# Wiegand.net
KiCad netlist of a schematic drawn in EAGLE
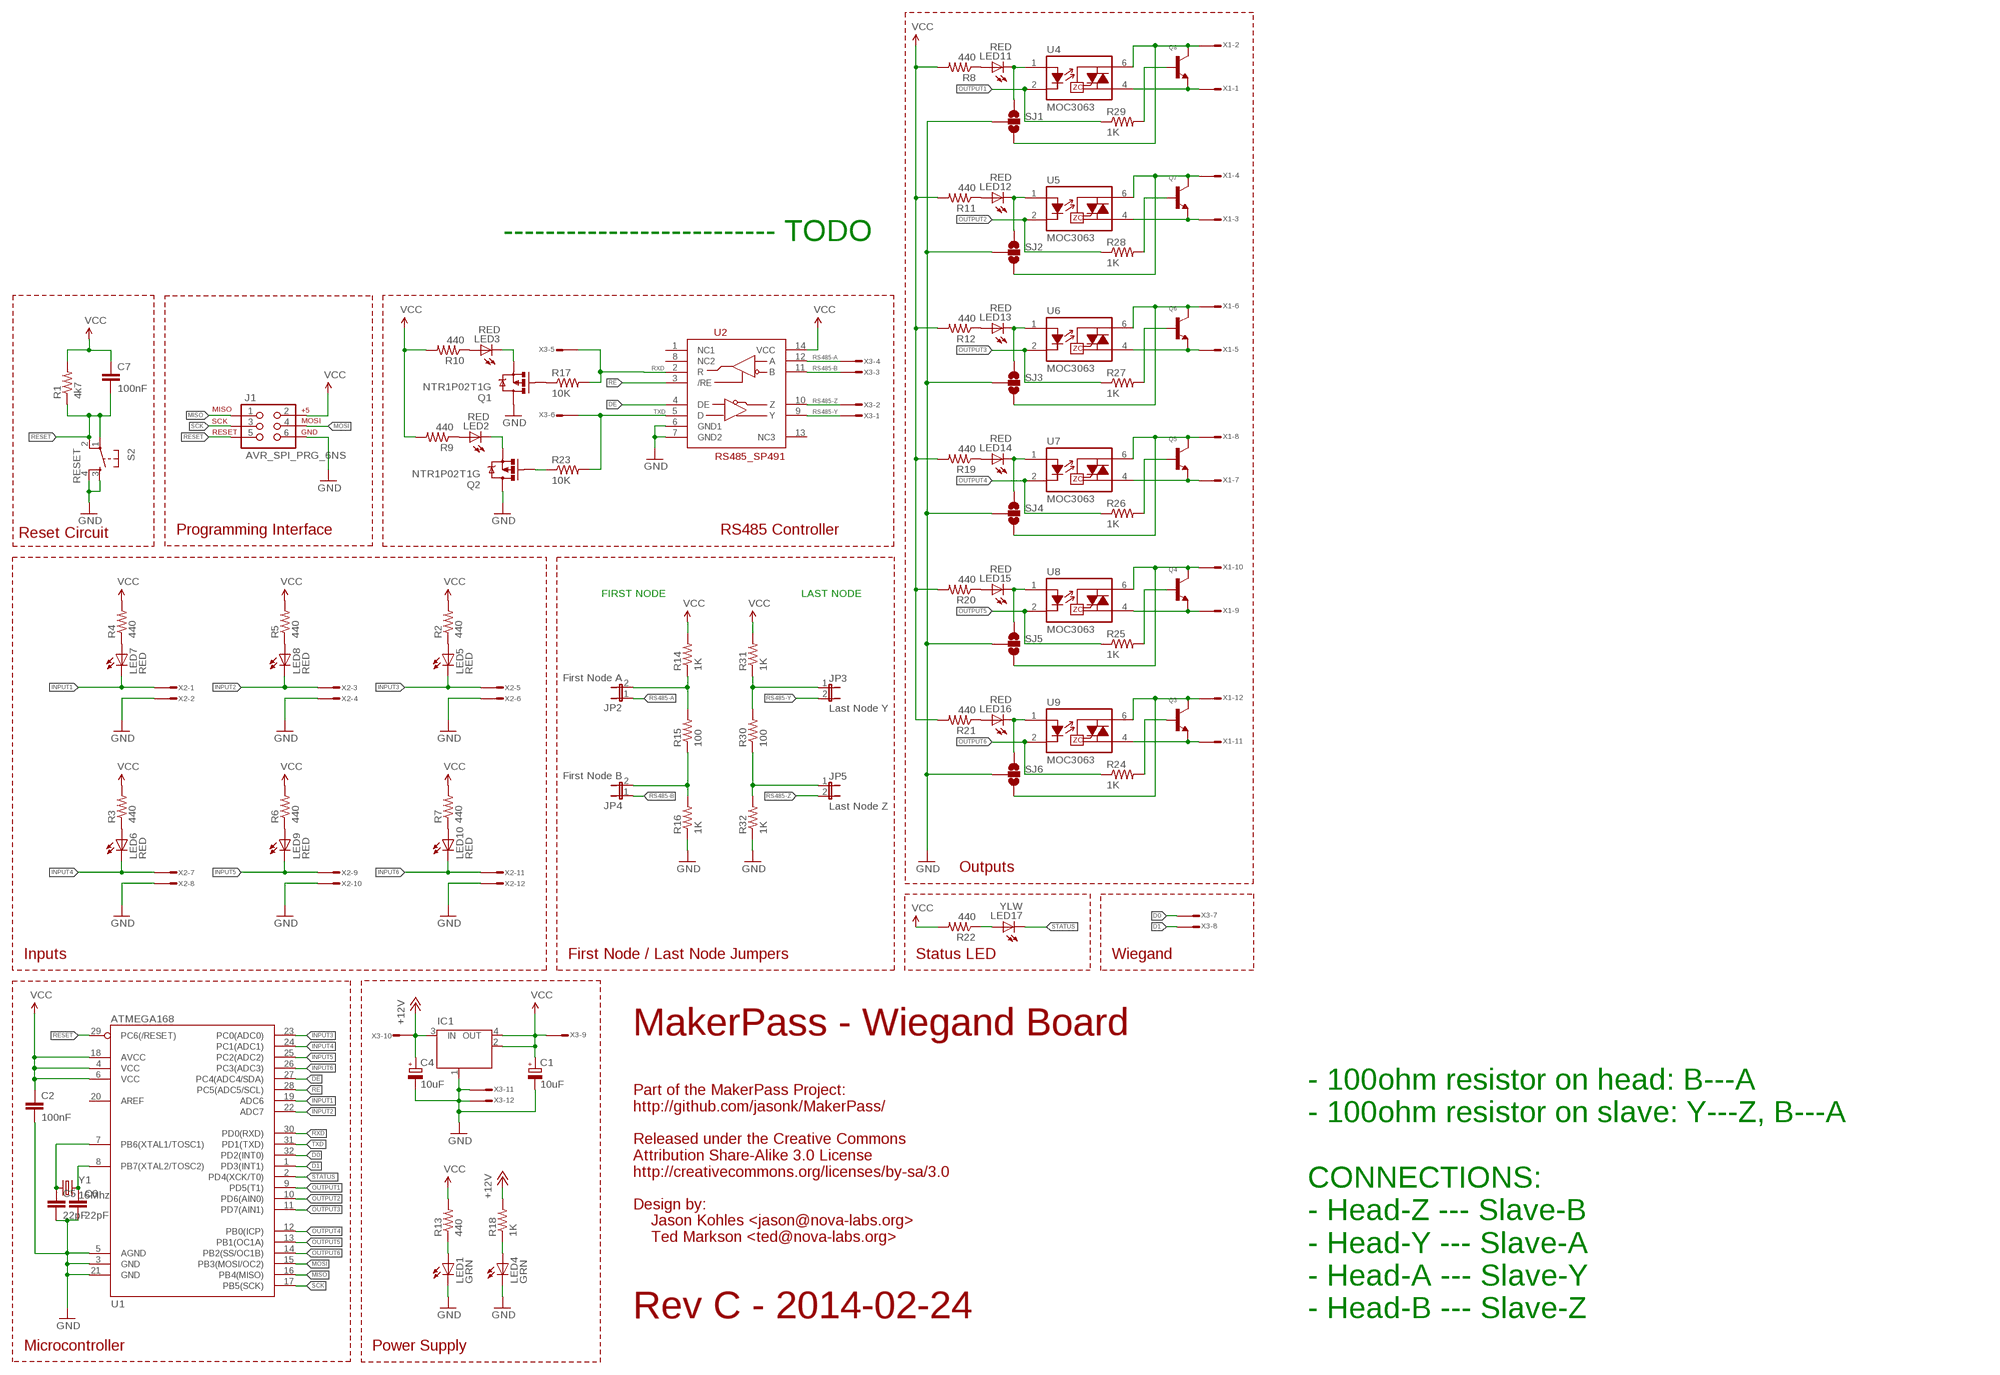
[diagram p0: schematic, sheet 1]

(export (version "E")
  (design (tool "Eeschema 10.0.6"))
  (components
    (comp (ref "C1")
      (value "10uF")
      (footprint "eagle-import:PANASONIC_D")
      (libsource (lib "eagle-import") (part "CPOL-EUD"))
    )
    (comp (ref "C2")
      (value "100nF")
      (footprint "eagle-import:0603-CAP")
      (libsource (lib "eagle-import") (part "CAP0603-CAP"))
    )
    (comp (ref "C4")
      (value "10uF")
      (footprint "eagle-import:PANASONIC_D")
      (libsource (lib "eagle-import") (part "CPOL-EUD"))
    )
    (comp (ref "C5")
      (value "22pF")
      (footprint "eagle-import:0603-CAP")
      (libsource (lib "eagle-import") (part "CAP0603-CAP"))
    )
    (comp (ref "C6")
      (value "22pF")
      (footprint "eagle-import:0603-CAP")
      (libsource (lib "eagle-import") (part "CAP0603-CAP"))
    )
    (comp (ref "C7")
      (value "100nF")
      (footprint "eagle-import:0603-CAP")
      (libsource (lib "eagle-import") (part "CAP0603-CAP"))
    )
    (comp (ref "IC1")
      (value "MC33269ST-3.3T3")
      (footprint "eagle-import:SOT223")
      (libsource (lib "eagle-import") (part "MC33269ST-3.3T3"))
    )
    (comp (ref "J1")
      (value "AVR_SPI_PRG_6NS")
      (footprint "eagle-import:2X3-NS")
      (libsource (lib "eagle-import") (part "AVR_SPI_PRG_6NS"))
    )
    (comp (ref "JP2")
      (value "First Node A")
      (footprint "eagle-import:1X02")
      (libsource (lib "eagle-import") (part "JUMPER-2PTH"))
    )
    (comp (ref "JP3")
      (value "Last Node Y")
      (footprint "eagle-import:1X02")
      (libsource (lib "eagle-import") (part "JUMPER-2PTH"))
    )
    (comp (ref "JP4")
      (value "First Node B")
      (footprint "eagle-import:1X02")
      (libsource (lib "eagle-import") (part "JUMPER-2PTH"))
    )
    (comp (ref "JP5")
      (value "Last Node Z")
      (footprint "eagle-import:1X02")
      (libsource (lib "eagle-import") (part "JUMPER-2PTH"))
    )
    (comp (ref "LED1")
      (value "GRN")
      (footprint "eagle-import:LED-805")
      (libsource (lib "eagle-import") (part "LED-0805"))
    )
    (comp (ref "LED2")
      (value "RED")
      (footprint "eagle-import:LED-805")
      (libsource (lib "eagle-import") (part "LED-0805"))
    )
    (comp (ref "LED3")
      (value "RED")
      (footprint "eagle-import:LED-805")
      (libsource (lib "eagle-import") (part "LED-0805"))
    )
    (comp (ref "LED4")
      (value "GRN")
      (footprint "eagle-import:LED-805")
      (libsource (lib "eagle-import") (part "LED-0805"))
    )
    (comp (ref "LED5")
      (value "RED")
      (footprint "eagle-import:LED-805")
      (libsource (lib "eagle-import") (part "LED-0805"))
    )
    (comp (ref "LED6")
      (value "RED")
      (footprint "eagle-import:LED-805")
      (libsource (lib "eagle-import") (part "LED-0805"))
    )
    (comp (ref "LED7")
      (value "RED")
      (footprint "eagle-import:LED-805")
      (libsource (lib "eagle-import") (part "LED-0805"))
    )
    (comp (ref "LED8")
      (value "RED")
      (footprint "eagle-import:LED-805")
      (libsource (lib "eagle-import") (part "LED-0805"))
    )
    (comp (ref "LED9")
      (value "RED")
      (footprint "eagle-import:LED-805")
      (libsource (lib "eagle-import") (part "LED-0805"))
    )
    (comp (ref "LED10")
      (value "RED")
      (footprint "eagle-import:LED-805")
      (libsource (lib "eagle-import") (part "LED-0805"))
    )
    (comp (ref "LED11")
      (value "RED")
      (footprint "eagle-import:LED-805")
      (libsource (lib "eagle-import") (part "LED-0805"))
    )
    (comp (ref "LED12")
      (value "RED")
      (footprint "eagle-import:LED-805")
      (libsource (lib "eagle-import") (part "LED-0805"))
    )
    (comp (ref "LED13")
      (value "RED")
      (footprint "eagle-import:LED-805")
      (libsource (lib "eagle-import") (part "LED-0805"))
    )
    (comp (ref "LED14")
      (value "RED")
      (footprint "eagle-import:LED-805")
      (libsource (lib "eagle-import") (part "LED-0805"))
    )
    (comp (ref "LED15")
      (value "RED")
      (footprint "eagle-import:LED-805")
      (libsource (lib "eagle-import") (part "LED-0805"))
    )
    (comp (ref "LED16")
      (value "RED")
      (footprint "eagle-import:LED-805")
      (libsource (lib "eagle-import") (part "LED-0805"))
    )
    (comp (ref "LED17")
      (value "YLW")
      (footprint "eagle-import:LED-805")
      (libsource (lib "eagle-import") (part "LED-0805"))
    )
    (comp (ref "Q1")
      (value "NTR1P02T1G")
      (footprint "eagle-import:SOT23-3")
      (libsource (lib "eagle-import") (part "MOSFET-PCHANNELSMD"))
    )
    (comp (ref "Q2")
      (value "NTR1P02T1G")
      (footprint "eagle-import:SOT23-3")
      (libsource (lib "eagle-import") (part "MOSFET-PCHANNELSMD"))
    )
    (comp (ref "Q3")
      (value "NPN-BEC-SOT23-3")
      (footprint "eagle-import:SOT23-3")
      (libsource (lib "eagle-import") (part "NPN-BEC-SOT23-3"))
    )
    (comp (ref "Q4")
      (value "NPN-BEC-SOT23-3")
      (footprint "eagle-import:SOT23-3")
      (libsource (lib "eagle-import") (part "NPN-BEC-SOT23-3"))
    )
    (comp (ref "Q5")
      (value "NPN-BEC-SOT23-3")
      (footprint "eagle-import:SOT23-3")
      (libsource (lib "eagle-import") (part "NPN-BEC-SOT23-3"))
    )
    (comp (ref "Q6")
      (value "NPN-BEC-SOT23-3")
      (footprint "eagle-import:SOT23-3")
      (libsource (lib "eagle-import") (part "NPN-BEC-SOT23-3"))
    )
    (comp (ref "Q7")
      (value "NPN-BEC-SOT23-3")
      (footprint "eagle-import:SOT23-3")
      (libsource (lib "eagle-import") (part "NPN-BEC-SOT23-3"))
    )
    (comp (ref "Q8")
      (value "NPN-BEC-SOT23-3")
      (footprint "eagle-import:SOT23-3")
      (libsource (lib "eagle-import") (part "NPN-BEC-SOT23-3"))
    )
    (comp (ref "R1")
      (value "4k7")
      (footprint "eagle-import:0603-RES")
      (libsource (lib "eagle-import") (part "RESISTOR0603-RES"))
    )
    (comp (ref "R2")
      (value "440")
      (footprint "eagle-import:0603-RES")
      (libsource (lib "eagle-import") (part "RESISTOR0603-RES"))
    )
    (comp (ref "R3")
      (value "440")
      (footprint "eagle-import:0603-RES")
      (libsource (lib "eagle-import") (part "RESISTOR0603-RES"))
    )
    (comp (ref "R4")
      (value "440")
      (footprint "eagle-import:0603-RES")
      (libsource (lib "eagle-import") (part "RESISTOR0603-RES"))
    )
    (comp (ref "R5")
      (value "440")
      (footprint "eagle-import:0603-RES")
      (libsource (lib "eagle-import") (part "RESISTOR0603-RES"))
    )
    (comp (ref "R6")
      (value "440")
      (footprint "eagle-import:0603-RES")
      (libsource (lib "eagle-import") (part "RESISTOR0603-RES"))
    )
    (comp (ref "R7")
      (value "440")
      (footprint "eagle-import:0603-RES")
      (libsource (lib "eagle-import") (part "RESISTOR0603-RES"))
    )
    (comp (ref "R8")
      (value "440")
      (footprint "eagle-import:0603-RES")
      (libsource (lib "eagle-import") (part "RESISTOR0603-RES"))
    )
    (comp (ref "R9")
      (value "440")
      (footprint "eagle-import:0603-RES")
      (libsource (lib "eagle-import") (part "RESISTOR0603-RES"))
    )
    (comp (ref "R10")
      (value "440")
      (footprint "eagle-import:0603-RES")
      (libsource (lib "eagle-import") (part "RESISTOR0603-RES"))
    )
    (comp (ref "R11")
      (value "440")
      (footprint "eagle-import:0603-RES")
      (libsource (lib "eagle-import") (part "RESISTOR0603-RES"))
    )
    (comp (ref "R12")
      (value "440")
      (footprint "eagle-import:0603-RES")
      (libsource (lib "eagle-import") (part "RESISTOR0603-RES"))
    )
    (comp (ref "R13")
      (value "440")
      (footprint "eagle-import:0603-RES")
      (libsource (lib "eagle-import") (part "RESISTOR0603-RES"))
    )
    (comp (ref "R14")
      (value "1K")
      (footprint "eagle-import:0603-RES")
      (libsource (lib "eagle-import") (part "RESISTOR0603-RES"))
    )
    (comp (ref "R15")
      (value "100")
      (footprint "eagle-import:0603-RES")
      (libsource (lib "eagle-import") (part "RESISTOR0603-RES"))
    )
    (comp (ref "R16")
      (value "1K")
      (footprint "eagle-import:0603-RES")
      (libsource (lib "eagle-import") (part "RESISTOR0603-RES"))
    )
    (comp (ref "R17")
      (value "10K")
      (footprint "eagle-import:0603-RES")
      (libsource (lib "eagle-import") (part "RESISTOR0603-RES"))
    )
    (comp (ref "R18")
      (value "1K")
      (footprint "eagle-import:0603-RES")
      (libsource (lib "eagle-import") (part "RESISTOR0603-RES"))
    )
    (comp (ref "R19")
      (value "440")
      (footprint "eagle-import:0603-RES")
      (libsource (lib "eagle-import") (part "RESISTOR0603-RES"))
    )
    (comp (ref "R20")
      (value "440")
      (footprint "eagle-import:0603-RES")
      (libsource (lib "eagle-import") (part "RESISTOR0603-RES"))
    )
    (comp (ref "R21")
      (value "440")
      (footprint "eagle-import:0603-RES")
      (libsource (lib "eagle-import") (part "RESISTOR0603-RES"))
    )
    (comp (ref "R22")
      (value "440")
      (footprint "eagle-import:0603-RES")
      (libsource (lib "eagle-import") (part "RESISTOR0603-RES"))
    )
    (comp (ref "R23")
      (value "10K")
      (footprint "eagle-import:0603-RES")
      (libsource (lib "eagle-import") (part "RESISTOR0603-RES"))
    )
    (comp (ref "R24")
      (value "1K")
      (footprint "eagle-import:0603-RES")
      (libsource (lib "eagle-import") (part "RESISTOR0603-RES"))
    )
    (comp (ref "R25")
      (value "1K")
      (footprint "eagle-import:0603-RES")
      (libsource (lib "eagle-import") (part "RESISTOR0603-RES"))
    )
    (comp (ref "R26")
      (value "1K")
      (footprint "eagle-import:0603-RES")
      (libsource (lib "eagle-import") (part "RESISTOR0603-RES"))
    )
    (comp (ref "R27")
      (value "1K")
      (footprint "eagle-import:0603-RES")
      (libsource (lib "eagle-import") (part "RESISTOR0603-RES"))
    )
    (comp (ref "R28")
      (value "1K")
      (footprint "eagle-import:0603-RES")
      (libsource (lib "eagle-import") (part "RESISTOR0603-RES"))
    )
    (comp (ref "R29")
      (value "1K")
      (footprint "eagle-import:0603-RES")
      (libsource (lib "eagle-import") (part "RESISTOR0603-RES"))
    )
    (comp (ref "R30")
      (value "100")
      (footprint "eagle-import:0603-RES")
      (libsource (lib "eagle-import") (part "RESISTOR0603-RES"))
    )
    (comp (ref "R31")
      (value "1K")
      (footprint "eagle-import:0603-RES")
      (libsource (lib "eagle-import") (part "RESISTOR0603-RES"))
    )
    (comp (ref "R32")
      (value "1K")
      (footprint "eagle-import:0603-RES")
      (libsource (lib "eagle-import") (part "RESISTOR0603-RES"))
    )
    (comp (ref "S2")
      (value "RESET")
      (footprint "eagle-import:TACTILE_SWITCH_SMD")
      (libsource (lib "eagle-import") (part "TAC_SWITCHSMD"))
    )
    (comp (ref "SJ1")
      (value "SOLDERJUMPER_2WAYS")
      (footprint "eagle-import:SJ_3")
      (libsource (lib "eagle-import") (part "SOLDERJUMPER_2WAYS"))
    )
    (comp (ref "SJ2")
      (value "SOLDERJUMPER_2WAYS")
      (footprint "eagle-import:SJ_3")
      (libsource (lib "eagle-import") (part "SOLDERJUMPER_2WAYS"))
    )
    (comp (ref "SJ3")
      (value "SOLDERJUMPER_2WAYS")
      (footprint "eagle-import:SJ_3")
      (libsource (lib "eagle-import") (part "SOLDERJUMPER_2WAYS"))
    )
    (comp (ref "SJ4")
      (value "SOLDERJUMPER_2WAYS")
      (footprint "eagle-import:SJ_3")
      (libsource (lib "eagle-import") (part "SOLDERJUMPER_2WAYS"))
    )
    (comp (ref "SJ5")
      (value "SOLDERJUMPER_2WAYS")
      (footprint "eagle-import:SJ_3")
      (libsource (lib "eagle-import") (part "SOLDERJUMPER_2WAYS"))
    )
    (comp (ref "SJ6")
      (value "SOLDERJUMPER_2WAYS")
      (footprint "eagle-import:SJ_3")
      (libsource (lib "eagle-import") (part "SOLDERJUMPER_2WAYS"))
    )
    (comp (ref "U1")
      (value "ATMEGA168")
      (footprint "eagle-import:TQFP32-08")
      (libsource (lib "eagle-import") (part "ATMEGA168"))
    )
    (comp (ref "U2")
      (value "RS485_SP491")
      (footprint "eagle-import:SOIC-14")
      (libsource (lib "eagle-import") (part "RS485_SP491"))
    )
    (comp (ref "U4")
      (value "MOC3063")
      (footprint "eagle-import:DIP8SMD")
      (libsource (lib "eagle-import") (part "MOC3063S"))
    )
    (comp (ref "U5")
      (value "MOC3063")
      (footprint "eagle-import:DIP8SMD")
      (libsource (lib "eagle-import") (part "MOC3063S"))
    )
    (comp (ref "U6")
      (value "MOC3063")
      (footprint "eagle-import:DIP8SMD")
      (libsource (lib "eagle-import") (part "MOC3063S"))
    )
    (comp (ref "U7")
      (value "MOC3063")
      (footprint "eagle-import:DIP8SMD")
      (libsource (lib "eagle-import") (part "MOC3063S"))
    )
    (comp (ref "U8")
      (value "MOC3063")
      (footprint "eagle-import:DIP8SMD")
      (libsource (lib "eagle-import") (part "MOC3063S"))
    )
    (comp (ref "U9")
      (value "MOC3063")
      (footprint "eagle-import:DIP8SMD")
      (libsource (lib "eagle-import") (part "MOC3063S"))
    )
    (comp (ref "X1")
      (value "CON-1X12-TERMBLOCK-3.5MM")
      (footprint "eagle-import:CON-1X12-TERMBLOCK-3.5MM")
      (fields (field (name "MFG_PN") "OSTTE120104"))
      (libsource (lib "eagle-import") (part "CON-1X12-TERMBLOCK-3.5MM"))
    )
    (comp (ref "X2")
      (value "CON-1X12-TERMBLOCK-3.5MM")
      (footprint "eagle-import:CON-1X12-TERMBLOCK-3.5MM")
      (fields (field (name "MFG_PN") "OSTTE120104"))
      (libsource (lib "eagle-import") (part "CON-1X12-TERMBLOCK-3.5MM"))
    )
    (comp (ref "X3")
      (value "CON-1X12-TERMBLOCK-3.5MM")
      (footprint "eagle-import:CON-1X12-TERMBLOCK-3.5MM")
      (fields (field (name "MFG_PN") "OSTTE120104"))
      (libsource (lib "eagle-import") (part "CON-1X12-TERMBLOCK-3.5MM"))
    )
    (comp (ref "Y1")
      (value "16Mhz")
      (footprint "eagle-import:HC49UP")
      (libsource (lib "eagle-import") (part "CRYSTALSMD"))
    )
  )
  (nets
    (net (code "1") (name "+12V") (class "Default")
      (node (ref "C4") (pin "+") (pinfunction "+_+") (pintype "passive"))
      (node (ref "IC1") (pin "3") (pinfunction "IN_3") (pintype "input"))
      (node (ref "R18") (pin "2") (pinfunction "2_2") (pintype "passive"))
      (node (ref "X3") (pin "10") (pinfunction "S_10") (pintype "passive"))
    )
    (net (code "2") (name "D0") (class "Default")
      (node (ref "U1") (pin "32") (pinfunction "PD2(INT0)_32") (pintype "bidirectional"))
      (node (ref "X3") (pin "7") (pinfunction "S_7") (pintype "passive"))
    )
    (net (code "3") (name "D1") (class "Default")
      (node (ref "U1") (pin "1") (pinfunction "PD3(INT1)_1") (pintype "bidirectional"))
      (node (ref "X3") (pin "8") (pinfunction "S_8") (pintype "passive"))
    )
    (net (code "4") (name "DE") (class "Default")
      (node (ref "U1") (pin "27") (pinfunction "PC4(ADC4/SDA)_27") (pintype "bidirectional"))
      (node (ref "U2") (pin "4") (pinfunction "DE_4") (pintype "bidirectional"))
    )
    (net (code "5") (name "GND") (class "Default")
      (node (ref "C1") (pin "-") (pinfunction "-_-") (pintype "passive"))
      (node (ref "C2") (pin "2") (pinfunction "2_2") (pintype "passive"))
      (node (ref "C4") (pin "-") (pinfunction "-_-") (pintype "passive"))
      (node (ref "C5") (pin "2") (pinfunction "2_2") (pintype "passive"))
      (node (ref "C6") (pin "2") (pinfunction "2_2") (pintype "passive"))
      (node (ref "IC1") (pin "1") (pinfunction "GND/ADJ_1") (pintype "input"))
      (node (ref "J1") (pin "6") (pinfunction "6_6") (pintype "passive"))
      (node (ref "LED1") (pin "C") (pinfunction "C_C") (pintype "passive"))
      (node (ref "LED4") (pin "C") (pinfunction "C_C") (pintype "passive"))
      (node (ref "Q1") (pin "3") (pinfunction "D_3") (pintype "passive"))
      (node (ref "Q2") (pin "3") (pinfunction "D_3") (pintype "passive"))
      (node (ref "R16") (pin "1") (pinfunction "1_1") (pintype "passive"))
      (node (ref "R32") (pin "1") (pinfunction "1_1") (pintype "passive"))
      (node (ref "S2") (pin "3") (pinfunction "3_3") (pintype "passive"))
      (node (ref "S2") (pin "4") (pinfunction "4_4") (pintype "passive"))
      (node (ref "SJ1") (pin "2") (pinfunction "2_2") (pintype "passive"))
      (node (ref "SJ2") (pin "2") (pinfunction "2_2") (pintype "passive"))
      (node (ref "SJ3") (pin "2") (pinfunction "2_2") (pintype "passive"))
      (node (ref "SJ4") (pin "2") (pinfunction "2_2") (pintype "passive"))
      (node (ref "SJ5") (pin "2") (pinfunction "2_2") (pintype "passive"))
      (node (ref "SJ6") (pin "2") (pinfunction "2_2") (pintype "passive"))
      (node (ref "U1") (pin "21") (pinfunction "GND_21") (pintype "bidirectional"))
      (node (ref "U1") (pin "3") (pinfunction "GND_3") (pintype "bidirectional"))
      (node (ref "U1") (pin "5") (pinfunction "AGND_5") (pintype "bidirectional"))
      (node (ref "U2") (pin "6") (pinfunction "GND1_6") (pintype "bidirectional"))
      (node (ref "U2") (pin "7") (pinfunction "GND2_7") (pintype "bidirectional"))
      (node (ref "X2") (pin "10") (pinfunction "S_10") (pintype "passive"))
      (node (ref "X2") (pin "12") (pinfunction "S_12") (pintype "passive"))
      (node (ref "X2") (pin "2") (pinfunction "S_2") (pintype "passive"))
      (node (ref "X2") (pin "4") (pinfunction "S_4") (pintype "passive"))
      (node (ref "X2") (pin "6") (pinfunction "S_6") (pintype "passive"))
      (node (ref "X2") (pin "8") (pinfunction "S_8") (pintype "passive"))
      (node (ref "X3") (pin "11") (pinfunction "S_11") (pintype "passive"))
      (node (ref "X3") (pin "12") (pinfunction "S_12") (pintype "passive"))
    )
    (net (code "6") (name "INPUT1") (class "Default")
      (node (ref "LED7") (pin "C") (pinfunction "C_C") (pintype "passive"))
      (node (ref "U1") (pin "19") (pinfunction "ADC6_19") (pintype "bidirectional"))
      (node (ref "X2") (pin "1") (pinfunction "S_1") (pintype "passive"))
    )
    (net (code "7") (name "INPUT2") (class "Default")
      (node (ref "LED8") (pin "C") (pinfunction "C_C") (pintype "passive"))
      (node (ref "U1") (pin "22") (pinfunction "ADC7_22") (pintype "bidirectional"))
      (node (ref "X2") (pin "3") (pinfunction "S_3") (pintype "passive"))
    )
    (net (code "8") (name "INPUT3") (class "Default")
      (node (ref "LED5") (pin "C") (pinfunction "C_C") (pintype "passive"))
      (node (ref "U1") (pin "23") (pinfunction "PC0(ADC0)_23") (pintype "bidirectional"))
      (node (ref "X2") (pin "5") (pinfunction "S_5") (pintype "passive"))
    )
    (net (code "9") (name "INPUT4") (class "Default")
      (node (ref "LED6") (pin "C") (pinfunction "C_C") (pintype "passive"))
      (node (ref "U1") (pin "24") (pinfunction "PC1(ADC1)_24") (pintype "bidirectional"))
      (node (ref "X2") (pin "7") (pinfunction "S_7") (pintype "passive"))
    )
    (net (code "10") (name "INPUT5") (class "Default")
      (node (ref "LED9") (pin "C") (pinfunction "C_C") (pintype "passive"))
      (node (ref "U1") (pin "25") (pinfunction "PC2(ADC2)_25") (pintype "bidirectional"))
      (node (ref "X2") (pin "9") (pinfunction "S_9") (pintype "passive"))
    )
    (net (code "11") (name "INPUT6") (class "Default")
      (node (ref "LED10") (pin "C") (pinfunction "C_C") (pintype "passive"))
      (node (ref "U1") (pin "26") (pinfunction "PC3(ADC3)_26") (pintype "bidirectional"))
      (node (ref "X2") (pin "11") (pinfunction "S_11") (pintype "passive"))
    )
    (net (code "12") (name "MISO") (class "Default")
      (node (ref "J1") (pin "1") (pinfunction "1_1") (pintype "passive"))
      (node (ref "U1") (pin "16") (pinfunction "PB4(MISO)_16") (pintype "bidirectional"))
    )
    (net (code "13") (name "MOSI") (class "Default")
      (node (ref "J1") (pin "4") (pinfunction "4_4") (pintype "passive"))
      (node (ref "U1") (pin "15") (pinfunction "PB3(MOSI/OC2)_15") (pintype "bidirectional"))
    )
    (net (code "14") (name "Net-(JP2-Pad2)") (class "Default")
      (node (ref "JP2") (pin "2") (pinfunction "2_2") (pintype "passive"))
      (node (ref "R14") (pin "1") (pinfunction "1_1") (pintype "passive"))
      (node (ref "R15") (pin "2") (pinfunction "2_2") (pintype "passive"))
    )
    (net (code "15") (name "Net-(JP3-Pad1)") (class "Default")
      (node (ref "JP3") (pin "1") (pinfunction "1_1") (pintype "passive"))
      (node (ref "R30") (pin "2") (pinfunction "2_2") (pintype "passive"))
      (node (ref "R31") (pin "1") (pinfunction "1_1") (pintype "passive"))
    )
    (net (code "16") (name "Net-(JP4-Pad2)") (class "Default")
      (node (ref "JP4") (pin "2") (pinfunction "2_2") (pintype "passive"))
      (node (ref "R15") (pin "1") (pinfunction "1_1") (pintype "passive"))
      (node (ref "R16") (pin "2") (pinfunction "2_2") (pintype "passive"))
    )
    (net (code "17") (name "Net-(JP5-Pad1)") (class "Default")
      (node (ref "JP5") (pin "1") (pinfunction "1_1") (pintype "passive"))
      (node (ref "R30") (pin "1") (pinfunction "1_1") (pintype "passive"))
      (node (ref "R32") (pin "2") (pinfunction "2_2") (pintype "passive"))
    )
    (net (code "18") (name "Net-(LED1-PadA)") (class "Default")
      (node (ref "LED1") (pin "A") (pinfunction "A_A") (pintype "passive"))
      (node (ref "R13") (pin "1") (pinfunction "1_1") (pintype "passive"))
    )
    (net (code "19") (name "Net-(LED2-PadA)") (class "Default")
      (node (ref "LED2") (pin "A") (pinfunction "A_A") (pintype "passive"))
      (node (ref "R9") (pin "1") (pinfunction "1_1") (pintype "passive"))
    )
    (net (code "20") (name "Net-(LED3-PadA)") (class "Default")
      (node (ref "LED3") (pin "A") (pinfunction "A_A") (pintype "passive"))
      (node (ref "R10") (pin "1") (pinfunction "1_1") (pintype "passive"))
    )
    (net (code "21") (name "Net-(LED4-PadA)") (class "Default")
      (node (ref "LED4") (pin "A") (pinfunction "A_A") (pintype "passive"))
      (node (ref "R18") (pin "1") (pinfunction "1_1") (pintype "passive"))
    )
    (net (code "22") (name "Net-(LED5-PadA)") (class "Default")
      (node (ref "LED5") (pin "A") (pinfunction "A_A") (pintype "passive"))
      (node (ref "R2") (pin "1") (pinfunction "1_1") (pintype "passive"))
    )
    (net (code "23") (name "Net-(LED6-PadA)") (class "Default")
      (node (ref "LED6") (pin "A") (pinfunction "A_A") (pintype "passive"))
      (node (ref "R3") (pin "1") (pinfunction "1_1") (pintype "passive"))
    )
    (net (code "24") (name "Net-(LED7-PadA)") (class "Default")
      (node (ref "LED7") (pin "A") (pinfunction "A_A") (pintype "passive"))
      (node (ref "R4") (pin "1") (pinfunction "1_1") (pintype "passive"))
    )
    (net (code "25") (name "Net-(LED8-PadA)") (class "Default")
      (node (ref "LED8") (pin "A") (pinfunction "A_A") (pintype "passive"))
      (node (ref "R5") (pin "1") (pinfunction "1_1") (pintype "passive"))
    )
    (net (code "26") (name "Net-(LED9-PadA)") (class "Default")
      (node (ref "LED9") (pin "A") (pinfunction "A_A") (pintype "passive"))
      (node (ref "R6") (pin "1") (pinfunction "1_1") (pintype "passive"))
    )
    (net (code "27") (name "Net-(LED10-PadA)") (class "Default")
      (node (ref "LED10") (pin "A") (pinfunction "A_A") (pintype "passive"))
      (node (ref "R7") (pin "1") (pinfunction "1_1") (pintype "passive"))
    )
    (net (code "28") (name "Net-(LED11-PadA)") (class "Default")
      (node (ref "LED11") (pin "A") (pinfunction "A_A") (pintype "passive"))
      (node (ref "R8") (pin "1") (pinfunction "1_1") (pintype "passive"))
    )
    (net (code "29") (name "Net-(LED12-PadA)") (class "Default")
      (node (ref "LED12") (pin "A") (pinfunction "A_A") (pintype "passive"))
      (node (ref "R11") (pin "1") (pinfunction "1_1") (pintype "passive"))
    )
    (net (code "30") (name "Net-(LED13-PadA)") (class "Default")
      (node (ref "LED13") (pin "A") (pinfunction "A_A") (pintype "passive"))
      (node (ref "R12") (pin "1") (pinfunction "1_1") (pintype "passive"))
    )
    (net (code "31") (name "Net-(LED14-PadA)") (class "Default")
      (node (ref "LED14") (pin "A") (pinfunction "A_A") (pintype "passive"))
      (node (ref "R19") (pin "1") (pinfunction "1_1") (pintype "passive"))
    )
    (net (code "32") (name "Net-(LED15-PadA)") (class "Default")
      (node (ref "LED15") (pin "A") (pinfunction "A_A") (pintype "passive"))
      (node (ref "R20") (pin "1") (pinfunction "1_1") (pintype "passive"))
    )
    (net (code "33") (name "Net-(LED16-PadA)") (class "Default")
      (node (ref "LED16") (pin "A") (pinfunction "A_A") (pintype "passive"))
      (node (ref "R21") (pin "1") (pinfunction "1_1") (pintype "passive"))
    )
    (net (code "34") (name "Net-(LED17-PadA)") (class "Default")
      (node (ref "LED17") (pin "A") (pinfunction "A_A") (pintype "passive"))
      (node (ref "R22") (pin "1") (pinfunction "1_1") (pintype "passive"))
    )
    (net (code "35") (name "Net-(Q1-G)") (class "Default")
      (node (ref "Q1") (pin "1") (pinfunction "G_1") (pintype "passive"))
      (node (ref "R17") (pin "1") (pinfunction "1_1") (pintype "passive"))
    )
    (net (code "36") (name "Net-(Q1-S)") (class "Default")
      (node (ref "LED3") (pin "C") (pinfunction "C_C") (pintype "passive"))
      (node (ref "Q1") (pin "2") (pinfunction "S_2") (pintype "passive"))
    )
    (net (code "37") (name "Net-(Q2-G)") (class "Default")
      (node (ref "Q2") (pin "1") (pinfunction "G_1") (pintype "passive"))
      (node (ref "R23") (pin "1") (pinfunction "1_1") (pintype "passive"))
    )
    (net (code "38") (name "Net-(Q2-S)") (class "Default")
      (node (ref "LED2") (pin "C") (pinfunction "C_C") (pintype "passive"))
      (node (ref "Q2") (pin "2") (pinfunction "S_2") (pintype "passive"))
    )
    (net (code "39") (name "Net-(Q3-B)") (class "Default")
      (node (ref "Q3") (pin "1") (pinfunction "B_1") (pintype "passive"))
      (node (ref "R24") (pin "2") (pinfunction "2_2") (pintype "passive"))
    )
    (net (code "40") (name "Net-(Q3-C)") (class "Default")
      (node (ref "Q3") (pin "3") (pinfunction "C_3") (pintype "passive"))
      (node (ref "SJ6") (pin "3") (pinfunction "3_3") (pintype "passive"))
      (node (ref "U9") (pin "6") (pinfunction "T1_6") (pintype "bidirectional"))
      (node (ref "X1") (pin "12") (pinfunction "S_12") (pintype "passive"))
    )
    (net (code "41") (name "Net-(Q3-E)") (class "Default")
      (node (ref "Q3") (pin "2") (pinfunction "E_2") (pintype "passive"))
      (node (ref "U9") (pin "4") (pinfunction "T2_4") (pintype "bidirectional"))
      (node (ref "X1") (pin "11") (pinfunction "S_11") (pintype "passive"))
    )
    (net (code "42") (name "Net-(Q4-B)") (class "Default")
      (node (ref "Q4") (pin "1") (pinfunction "B_1") (pintype "passive"))
      (node (ref "R25") (pin "2") (pinfunction "2_2") (pintype "passive"))
    )
    (net (code "43") (name "Net-(Q4-C)") (class "Default")
      (node (ref "Q4") (pin "3") (pinfunction "C_3") (pintype "passive"))
      (node (ref "SJ5") (pin "3") (pinfunction "3_3") (pintype "passive"))
      (node (ref "U8") (pin "6") (pinfunction "T1_6") (pintype "bidirectional"))
      (node (ref "X1") (pin "10") (pinfunction "S_10") (pintype "passive"))
    )
    (net (code "44") (name "Net-(Q4-E)") (class "Default")
      (node (ref "Q4") (pin "2") (pinfunction "E_2") (pintype "passive"))
      (node (ref "U8") (pin "4") (pinfunction "T2_4") (pintype "bidirectional"))
      (node (ref "X1") (pin "9") (pinfunction "S_9") (pintype "passive"))
    )
    (net (code "45") (name "Net-(Q5-B)") (class "Default")
      (node (ref "Q5") (pin "1") (pinfunction "B_1") (pintype "passive"))
      (node (ref "R26") (pin "2") (pinfunction "2_2") (pintype "passive"))
    )
    (net (code "46") (name "Net-(Q5-C)") (class "Default")
      (node (ref "Q5") (pin "3") (pinfunction "C_3") (pintype "passive"))
      (node (ref "SJ4") (pin "3") (pinfunction "3_3") (pintype "passive"))
      (node (ref "U7") (pin "6") (pinfunction "T1_6") (pintype "bidirectional"))
      (node (ref "X1") (pin "8") (pinfunction "S_8") (pintype "passive"))
    )
    (net (code "47") (name "Net-(Q5-E)") (class "Default")
      (node (ref "Q5") (pin "2") (pinfunction "E_2") (pintype "passive"))
      (node (ref "U7") (pin "4") (pinfunction "T2_4") (pintype "bidirectional"))
      (node (ref "X1") (pin "7") (pinfunction "S_7") (pintype "passive"))
    )
    (net (code "48") (name "Net-(Q6-B)") (class "Default")
      (node (ref "Q6") (pin "1") (pinfunction "B_1") (pintype "passive"))
      (node (ref "R27") (pin "2") (pinfunction "2_2") (pintype "passive"))
    )
    (net (code "49") (name "Net-(Q6-C)") (class "Default")
      (node (ref "Q6") (pin "3") (pinfunction "C_3") (pintype "passive"))
      (node (ref "SJ3") (pin "3") (pinfunction "3_3") (pintype "passive"))
      (node (ref "U6") (pin "6") (pinfunction "T1_6") (pintype "bidirectional"))
      (node (ref "X1") (pin "6") (pinfunction "S_6") (pintype "passive"))
    )
    (net (code "50") (name "Net-(Q6-E)") (class "Default")
      (node (ref "Q6") (pin "2") (pinfunction "E_2") (pintype "passive"))
      (node (ref "U6") (pin "4") (pinfunction "T2_4") (pintype "bidirectional"))
      (node (ref "X1") (pin "5") (pinfunction "S_5") (pintype "passive"))
    )
    (net (code "51") (name "Net-(Q7-B)") (class "Default")
      (node (ref "Q7") (pin "1") (pinfunction "B_1") (pintype "passive"))
      (node (ref "R28") (pin "2") (pinfunction "2_2") (pintype "passive"))
    )
    (net (code "52") (name "Net-(Q7-C)") (class "Default")
      (node (ref "Q7") (pin "3") (pinfunction "C_3") (pintype "passive"))
      (node (ref "SJ2") (pin "3") (pinfunction "3_3") (pintype "passive"))
      (node (ref "U5") (pin "6") (pinfunction "T1_6") (pintype "bidirectional"))
      (node (ref "X1") (pin "4") (pinfunction "S_4") (pintype "passive"))
    )
    (net (code "53") (name "Net-(Q7-E)") (class "Default")
      (node (ref "Q7") (pin "2") (pinfunction "E_2") (pintype "passive"))
      (node (ref "U5") (pin "4") (pinfunction "T2_4") (pintype "bidirectional"))
      (node (ref "X1") (pin "3") (pinfunction "S_3") (pintype "passive"))
    )
    (net (code "54") (name "Net-(Q8-B)") (class "Default")
      (node (ref "Q8") (pin "1") (pinfunction "B_1") (pintype "passive"))
      (node (ref "R29") (pin "2") (pinfunction "2_2") (pintype "passive"))
    )
    (net (code "55") (name "Net-(Q8-C)") (class "Default")
      (node (ref "Q8") (pin "3") (pinfunction "C_3") (pintype "passive"))
      (node (ref "SJ1") (pin "3") (pinfunction "3_3") (pintype "passive"))
      (node (ref "U4") (pin "6") (pinfunction "T1_6") (pintype "bidirectional"))
      (node (ref "X1") (pin "2") (pinfunction "S_2") (pintype "passive"))
    )
    (net (code "56") (name "Net-(Q8-E)") (class "Default")
      (node (ref "Q8") (pin "2") (pinfunction "E_2") (pintype "passive"))
      (node (ref "U4") (pin "4") (pinfunction "T2_4") (pintype "bidirectional"))
      (node (ref "X1") (pin "1") (pinfunction "S_1") (pintype "passive"))
    )
    (net (code "57") (name "Net-(U1-PB6(XTAL1{slash}TOSC1))") (class "Default")
      (node (ref "C5") (pin "1") (pinfunction "1_1") (pintype "passive"))
      (node (ref "U1") (pin "7") (pinfunction "PB6(XTAL1/TOSC1)_7") (pintype "bidirectional"))
      (node (ref "Y1") (pin "1") (pinfunction "1_1") (pintype "passive"))
    )
    (net (code "58") (name "Net-(U1-PB7(XTAL2{slash}TOSC2))") (class "Default")
      (node (ref "C6") (pin "1") (pinfunction "1_1") (pintype "passive"))
      (node (ref "U1") (pin "8") (pinfunction "PB7(XTAL2/TOSC2)_8") (pintype "bidirectional"))
      (node (ref "Y1") (pin "2") (pinfunction "2_2") (pintype "passive"))
    )
    (net (code "59") (name "Net-(U4-A)") (class "Default")
      (node (ref "LED11") (pin "C") (pinfunction "C_C") (pintype "passive"))
      (node (ref "SJ1") (pin "1") (pinfunction "1_1") (pintype "passive"))
      (node (ref "U4") (pin "1") (pinfunction "A_1") (pintype "bidirectional"))
    )
    (net (code "60") (name "Net-(U5-A)") (class "Default")
      (node (ref "LED12") (pin "C") (pinfunction "C_C") (pintype "passive"))
      (node (ref "SJ2") (pin "1") (pinfunction "1_1") (pintype "passive"))
      (node (ref "U5") (pin "1") (pinfunction "A_1") (pintype "bidirectional"))
    )
    (net (code "61") (name "Net-(U6-A)") (class "Default")
      (node (ref "LED13") (pin "C") (pinfunction "C_C") (pintype "passive"))
      (node (ref "SJ3") (pin "1") (pinfunction "1_1") (pintype "passive"))
      (node (ref "U6") (pin "1") (pinfunction "A_1") (pintype "bidirectional"))
    )
    (net (code "62") (name "Net-(U7-A)") (class "Default")
      (node (ref "LED14") (pin "C") (pinfunction "C_C") (pintype "passive"))
      (node (ref "SJ4") (pin "1") (pinfunction "1_1") (pintype "passive"))
      (node (ref "U7") (pin "1") (pinfunction "A_1") (pintype "bidirectional"))
    )
    (net (code "63") (name "Net-(U8-A)") (class "Default")
      (node (ref "LED15") (pin "C") (pinfunction "C_C") (pintype "passive"))
      (node (ref "SJ5") (pin "1") (pinfunction "1_1") (pintype "passive"))
      (node (ref "U8") (pin "1") (pinfunction "A_1") (pintype "bidirectional"))
    )
    (net (code "64") (name "Net-(U9-A)") (class "Default")
      (node (ref "LED16") (pin "C") (pinfunction "C_C") (pintype "passive"))
      (node (ref "SJ6") (pin "1") (pinfunction "1_1") (pintype "passive"))
      (node (ref "U9") (pin "1") (pinfunction "A_1") (pintype "bidirectional"))
    )
    (net (code "65") (name "OUTPUT1") (class "Default")
      (node (ref "R29") (pin "1") (pinfunction "1_1") (pintype "passive"))
      (node (ref "U1") (pin "9") (pinfunction "PD5(T1)_9") (pintype "bidirectional"))
      (node (ref "U4") (pin "2") (pinfunction "K_2") (pintype "bidirectional"))
    )
    (net (code "66") (name "OUTPUT2") (class "Default")
      (node (ref "R28") (pin "1") (pinfunction "1_1") (pintype "passive"))
      (node (ref "U1") (pin "10") (pinfunction "PD6(AIN0)_10") (pintype "bidirectional"))
      (node (ref "U5") (pin "2") (pinfunction "K_2") (pintype "bidirectional"))
    )
    (net (code "67") (name "OUTPUT3") (class "Default")
      (node (ref "R27") (pin "1") (pinfunction "1_1") (pintype "passive"))
      (node (ref "U1") (pin "11") (pinfunction "PD7(AIN1)_11") (pintype "bidirectional"))
      (node (ref "U6") (pin "2") (pinfunction "K_2") (pintype "bidirectional"))
    )
    (net (code "68") (name "OUTPUT4") (class "Default")
      (node (ref "R26") (pin "1") (pinfunction "1_1") (pintype "passive"))
      (node (ref "U1") (pin "12") (pinfunction "PB0(ICP)_12") (pintype "bidirectional"))
      (node (ref "U7") (pin "2") (pinfunction "K_2") (pintype "bidirectional"))
    )
    (net (code "69") (name "OUTPUT5") (class "Default")
      (node (ref "R25") (pin "1") (pinfunction "1_1") (pintype "passive"))
      (node (ref "U1") (pin "13") (pinfunction "PB1(OC1A)_13") (pintype "bidirectional"))
      (node (ref "U8") (pin "2") (pinfunction "K_2") (pintype "bidirectional"))
    )
    (net (code "70") (name "OUTPUT6") (class "Default")
      (node (ref "R24") (pin "1") (pinfunction "1_1") (pintype "passive"))
      (node (ref "U1") (pin "14") (pinfunction "PB2(SS/OC1B)_14") (pintype "bidirectional"))
      (node (ref "U9") (pin "2") (pinfunction "K_2") (pintype "bidirectional"))
    )
    (net (code "71") (name "RE") (class "Default")
      (node (ref "U1") (pin "28") (pinfunction "PC5(ADC5/SCL)_28") (pintype "bidirectional"))
      (node (ref "U2") (pin "3") (pinfunction "/RE_3") (pintype "bidirectional"))
    )
    (net (code "72") (name "RESET") (class "Default")
      (node (ref "C7") (pin "2") (pinfunction "2_2") (pintype "passive"))
      (node (ref "J1") (pin "5") (pinfunction "5_5") (pintype "passive"))
      (node (ref "R1") (pin "1") (pinfunction "1_1") (pintype "passive"))
      (node (ref "S2") (pin "1") (pinfunction "1_1") (pintype "passive"))
      (node (ref "S2") (pin "2") (pinfunction "2_2") (pintype "passive"))
      (node (ref "U1") (pin "29") (pinfunction "PC6(/RESET)_29") (pintype "bidirectional"))
    )
    (net (code "73") (name "RS485-A") (class "Default")
      (node (ref "JP2") (pin "1") (pinfunction "1_1") (pintype "passive"))
      (node (ref "U2") (pin "12") (pinfunction "A_12") (pintype "bidirectional"))
      (node (ref "X3") (pin "4") (pinfunction "S_4") (pintype "passive"))
    )
    (net (code "74") (name "RS485-B") (class "Default")
      (node (ref "JP4") (pin "1") (pinfunction "1_1") (pintype "passive"))
      (node (ref "U2") (pin "11") (pinfunction "B_11") (pintype "bidirectional"))
      (node (ref "X3") (pin "3") (pinfunction "S_3") (pintype "passive"))
    )
    (net (code "75") (name "RS485-Y") (class "Default")
      (node (ref "JP3") (pin "2") (pinfunction "2_2") (pintype "passive"))
      (node (ref "U2") (pin "9") (pinfunction "Y_9") (pintype "bidirectional"))
      (node (ref "X3") (pin "1") (pinfunction "S_1") (pintype "passive"))
    )
    (net (code "76") (name "RS485-Z") (class "Default")
      (node (ref "JP5") (pin "2") (pinfunction "2_2") (pintype "passive"))
      (node (ref "U2") (pin "10") (pinfunction "Z_10") (pintype "bidirectional"))
      (node (ref "X3") (pin "2") (pinfunction "S_2") (pintype "passive"))
    )
    (net (code "77") (name "RXD") (class "Default")
      (node (ref "R17") (pin "2") (pinfunction "2_2") (pintype "passive"))
      (node (ref "U1") (pin "30") (pinfunction "PD0(RXD)_30") (pintype "bidirectional"))
      (node (ref "U2") (pin "2") (pinfunction "R_2") (pintype "bidirectional"))
      (node (ref "X3") (pin "5") (pinfunction "S_5") (pintype "passive"))
    )
    (net (code "78") (name "SCK") (class "Default")
      (node (ref "J1") (pin "3") (pinfunction "3_3") (pintype "passive"))
      (node (ref "U1") (pin "17") (pinfunction "PB5(SCK)_17") (pintype "bidirectional"))
    )
    (net (code "79") (name "STATUS") (class "Default")
      (node (ref "LED17") (pin "C") (pinfunction "C_C") (pintype "passive"))
      (node (ref "U1") (pin "2") (pinfunction "PD4(XCK/T0)_2") (pintype "bidirectional"))
    )
    (net (code "80") (name "TXD") (class "Default")
      (node (ref "R23") (pin "2") (pinfunction "2_2") (pintype "passive"))
      (node (ref "U1") (pin "31") (pinfunction "PD1(TXD)_31") (pintype "bidirectional"))
      (node (ref "U2") (pin "5") (pinfunction "D_5") (pintype "bidirectional"))
      (node (ref "X3") (pin "6") (pinfunction "S_6") (pintype "passive"))
    )
    (net (code "81") (name "VCC") (class "Default")
      (node (ref "C1") (pin "+") (pinfunction "+_+") (pintype "passive"))
      (node (ref "C2") (pin "1") (pinfunction "1_1") (pintype "passive"))
      (node (ref "C7") (pin "1") (pinfunction "1_1") (pintype "passive"))
      (node (ref "IC1") (pin "2") (pinfunction "OUT_2") (pintype "passive"))
      (node (ref "IC1") (pin "4") (pinfunction "OUT_4") (pintype "passive"))
      (node (ref "J1") (pin "2") (pinfunction "2_2") (pintype "passive"))
      (node (ref "R1") (pin "2") (pinfunction "2_2") (pintype "passive"))
      (node (ref "R10") (pin "2") (pinfunction "2_2") (pintype "passive"))
      (node (ref "R11") (pin "2") (pinfunction "2_2") (pintype "passive"))
      (node (ref "R12") (pin "2") (pinfunction "2_2") (pintype "passive"))
      (node (ref "R13") (pin "2") (pinfunction "2_2") (pintype "passive"))
      (node (ref "R14") (pin "2") (pinfunction "2_2") (pintype "passive"))
      (node (ref "R19") (pin "2") (pinfunction "2_2") (pintype "passive"))
      (node (ref "R2") (pin "2") (pinfunction "2_2") (pintype "passive"))
      (node (ref "R20") (pin "2") (pinfunction "2_2") (pintype "passive"))
      (node (ref "R21") (pin "2") (pinfunction "2_2") (pintype "passive"))
      (node (ref "R22") (pin "2") (pinfunction "2_2") (pintype "passive"))
      (node (ref "R3") (pin "2") (pinfunction "2_2") (pintype "passive"))
      (node (ref "R31") (pin "2") (pinfunction "2_2") (pintype "passive"))
      (node (ref "R4") (pin "2") (pinfunction "2_2") (pintype "passive"))
      (node (ref "R5") (pin "2") (pinfunction "2_2") (pintype "passive"))
      (node (ref "R6") (pin "2") (pinfunction "2_2") (pintype "passive"))
      (node (ref "R7") (pin "2") (pinfunction "2_2") (pintype "passive"))
      (node (ref "R8") (pin "2") (pinfunction "2_2") (pintype "passive"))
      (node (ref "R9") (pin "2") (pinfunction "2_2") (pintype "passive"))
      (node (ref "U1") (pin "18") (pinfunction "AVCC_18") (pintype "bidirectional"))
      (node (ref "U1") (pin "4") (pinfunction "VCC_4") (pintype "bidirectional"))
      (node (ref "U1") (pin "6") (pinfunction "VCC_6") (pintype "bidirectional"))
      (node (ref "U2") (pin "14") (pinfunction "VCC_14") (pintype "bidirectional"))
      (node (ref "X3") (pin "9") (pinfunction "S_9") (pintype "passive"))
    )
    (net (code "82") (name "unconnected-(U1-AREF-Pad20)") (class "Default")
      (node (ref "U1") (pin "20") (pinfunction "AREF_20") (pintype "bidirectional"))
    )
    (net (code "83") (name "unconnected-(U2-NC1-Pad1)") (class "Default")
      (node (ref "U2") (pin "1") (pinfunction "NC1_1") (pintype "bidirectional"))
    )
    (net (code "84") (name "unconnected-(U2-NC2-Pad8)") (class "Default")
      (node (ref "U2") (pin "8") (pinfunction "NC2_8") (pintype "bidirectional"))
    )
    (net (code "85") (name "unconnected-(U2-NC3-Pad13)") (class "Default")
      (node (ref "U2") (pin "13") (pinfunction "NC3_13") (pintype "bidirectional"))
    )
  )
)
